# Launch_Tower_Ignition_Board_v6-0.net
KiCad netlist of a schematic drawn in EAGLE
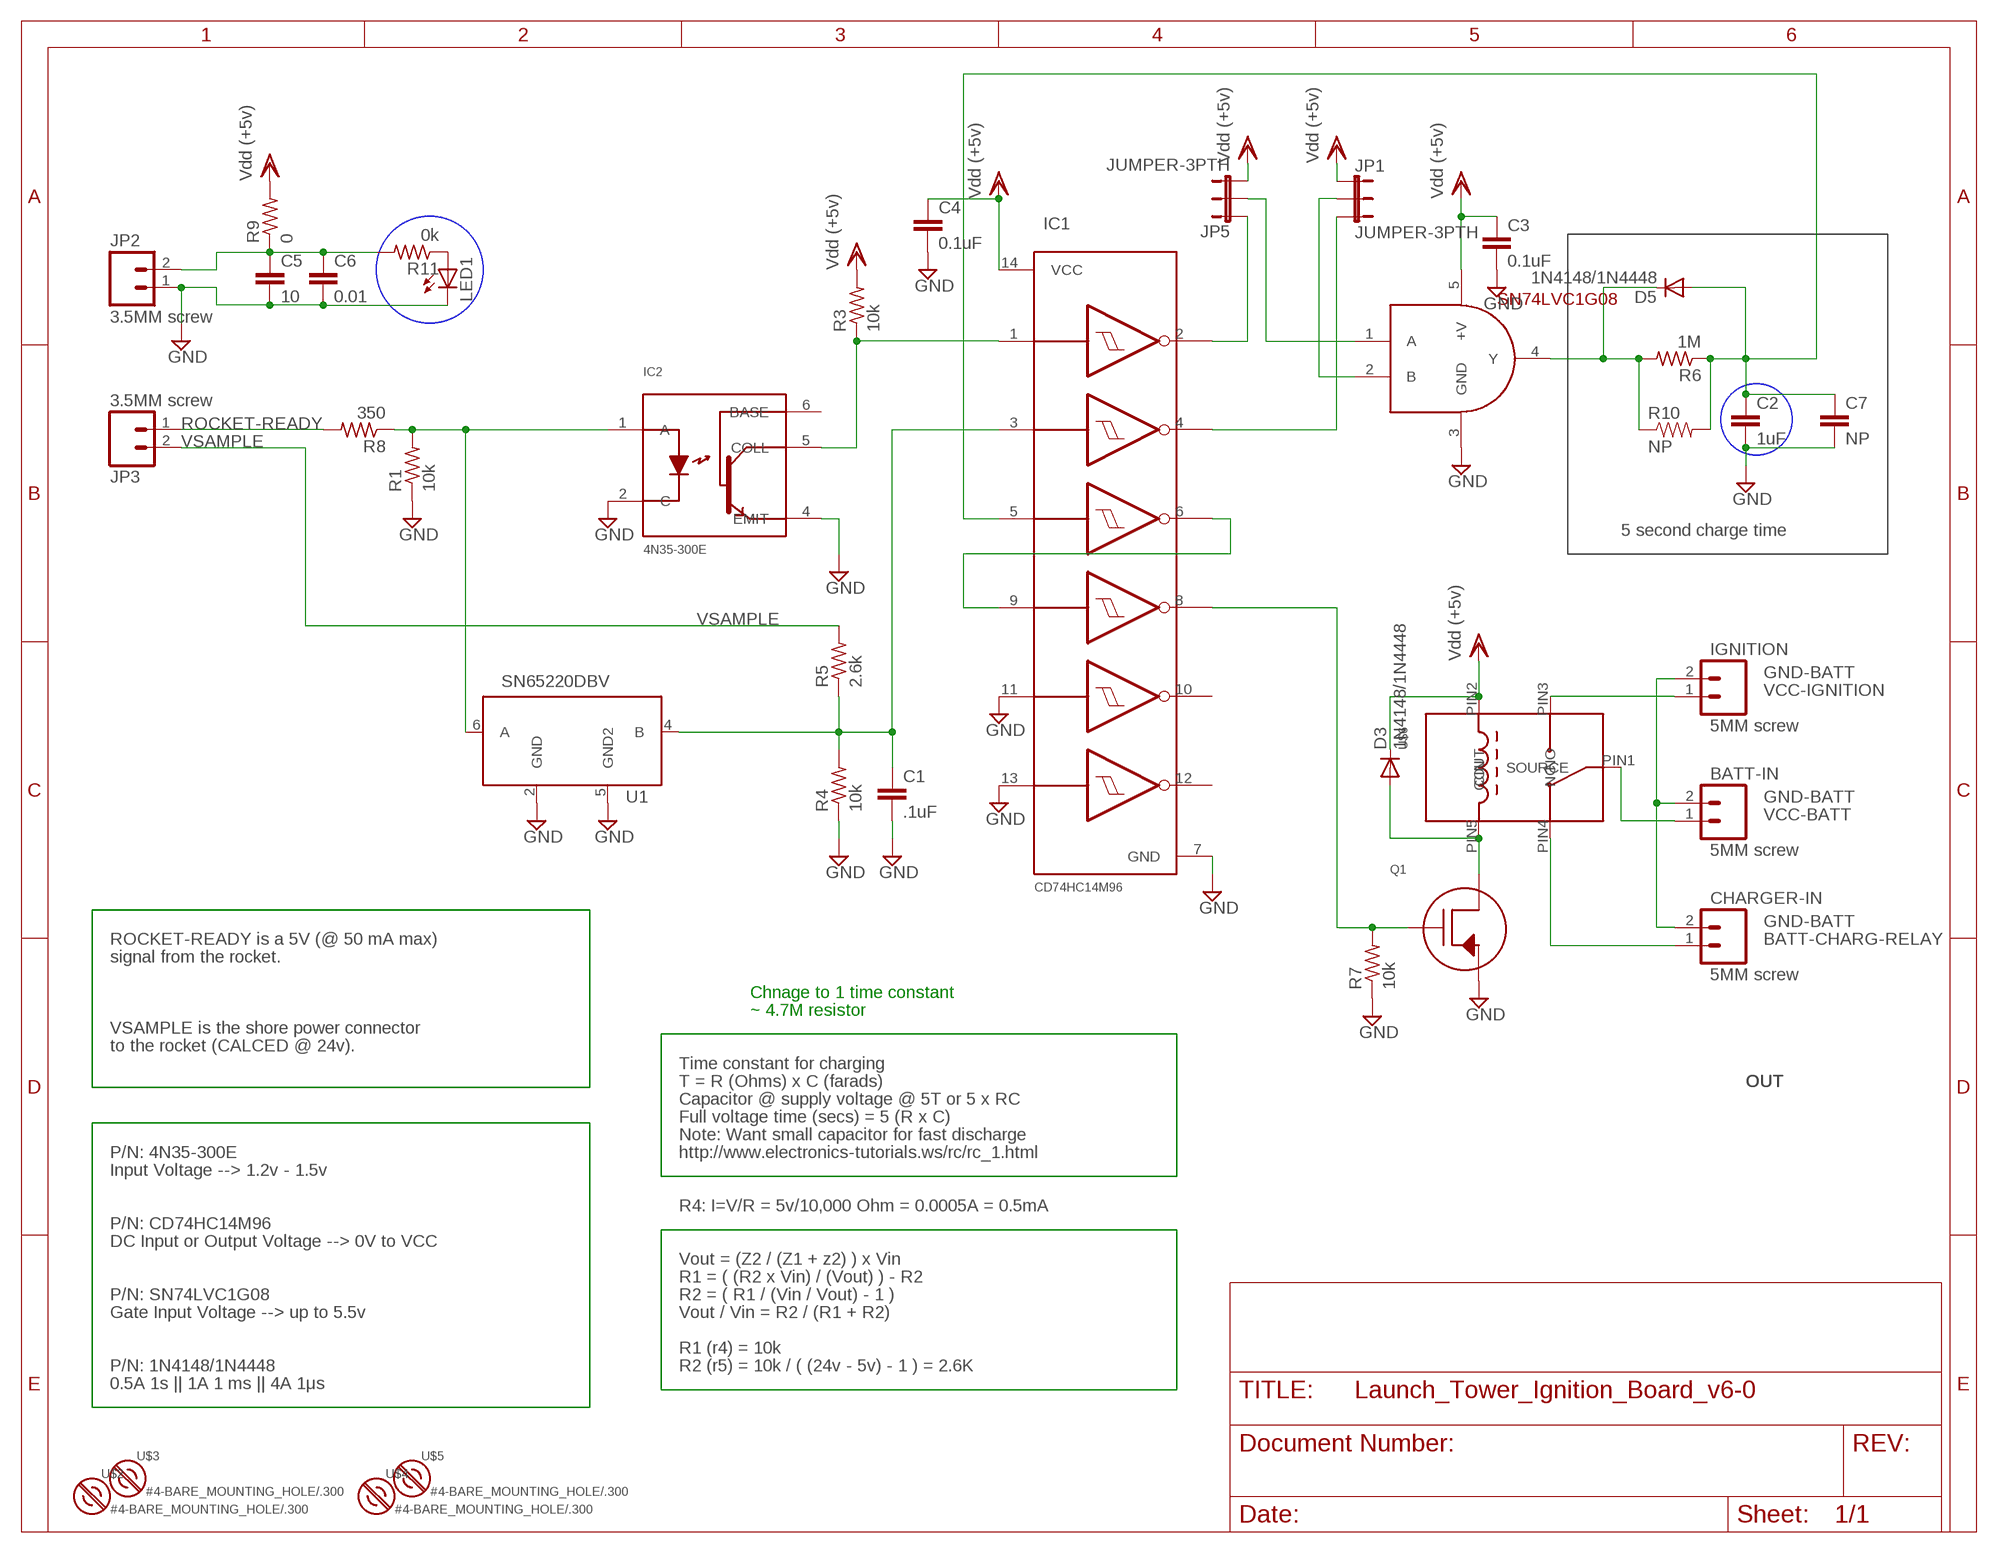
[diagram p0: schematic, sheet 1]

(export (version "E")
  (design (tool "Eeschema 10.0.6"))
  (components
    (comp (ref "BATT-IN")
      (value "5MM screw")
      (footprint "eagle-import:SCREWTERMINAL-5MM-2")
      (libsource (lib "eagle-import") (part "M025MM"))
    )
    (comp (ref "C1")
      (value ".1uF")
      (footprint "eagle-import:0805-B-NOSILK")
      (libsource (lib "eagle-import") (part "C-EU0805-B-NOSILK"))
    )
    (comp (ref "C2")
      (value "1uF")
      (footprint "eagle-import:0805-B-NOSILK")
      (libsource (lib "eagle-import") (part "C-EU0805-B-NOSILK"))
    )
    (comp (ref "C3")
      (value "0.1uF")
      (footprint "eagle-import:0805-B-NOSILK")
      (libsource (lib "eagle-import") (part "C-EU0805-B-NOSILK"))
    )
    (comp (ref "C4")
      (value "0.1uF")
      (footprint "eagle-import:0805-B-NOSILK")
      (libsource (lib "eagle-import") (part "C-EU0805-B-NOSILK"))
    )
    (comp (ref "C5")
      (value "10")
      (footprint "eagle-import:0805-B-NOSILK")
      (libsource (lib "eagle-import") (part "C-EU0805-B-NOSILK"))
    )
    (comp (ref "C6")
      (value "0.01")
      (footprint "eagle-import:0805-B-NOSILK")
      (libsource (lib "eagle-import") (part "C-EU0805-B-NOSILK"))
    )
    (comp (ref "C7")
      (value "NP")
      (footprint "eagle-import:CAP-PTH-SMALL")
      (libsource (lib "eagle-import") (part "CAPPTH"))
    )
    (comp (ref "CHARGER-IN")
      (value "5MM screw")
      (footprint "eagle-import:SCREWTERMINAL-5MM-2")
      (libsource (lib "eagle-import") (part "M025MM"))
    )
    (comp (ref "D3")
      (value "1N4148/1N4448")
      (footprint "eagle-import:DIODE-1N4001")
      (libsource (lib "eagle-import") (part "DIODEPTH"))
    )
    (comp (ref "D5")
      (value "1N4148/1N4448")
      (footprint "eagle-import:DIODE-1N4001")
      (libsource (lib "eagle-import") (part "DIODEPTH"))
    )
    (comp (ref "IC1")
      (value "INVERT GATES")
      (footprint "eagle-import:INVERTSOIC14")
      (libsource (lib "eagle-import") (part "HEX_INV_SHMITT_TRIG"))
    )
    (comp (ref "IC2")
      (value "OPTOISOLATOR")
      (footprint "eagle-import:4N35-300E")
      (libsource (lib "eagle-import") (part "OPTOISOLATOR"))
    )
    (comp (ref "IGNITION")
      (value "5MM screw")
      (footprint "eagle-import:SCREWTERMINAL-5MM-2")
      (libsource (lib "eagle-import") (part "M025MM"))
    )
    (comp (ref "JP1")
      (value "JUMPER-3PTH")
      (footprint "eagle-import:1X03")
      (libsource (lib "eagle-import") (part "JUMPER-3PTH"))
    )
    (comp (ref "JP2")
      (value "3.5MM screw")
      (footprint "eagle-import:SCREWTERMINAL-3.5MM-2")
      (libsource (lib "eagle-import") (part "M023.5MM"))
    )
    (comp (ref "JP3")
      (value "3.5MM screw")
      (footprint "eagle-import:SCREWTERMINAL-3.5MM-2")
      (libsource (lib "eagle-import") (part "M023.5MM"))
    )
    (comp (ref "JP5")
      (value "JUMPER-3PTH")
      (footprint "eagle-import:1X03")
      (libsource (lib "eagle-import") (part "JUMPER-3PTH"))
    )
    (comp (ref "LED1")
      (value "LED-FKIT-1206")
      (footprint "eagle-import:FKIT-LED-1206")
      (libsource (lib "eagle-import") (part "LED-FKIT-1206"))
    )
    (comp (ref "Q1")
      (value "NMOSFET")
      (footprint "eagle-import:FETSO-8")
      (libsource (lib "eagle-import") (part "NMOSFET"))
    )
    (comp (ref "R1")
      (value "10k")
      (footprint "eagle-import:0805-B-NOSILK")
      (libsource (lib "eagle-import") (part "R-US_0805-B-NOSILK"))
    )
    (comp (ref "R3")
      (value "10k")
      (footprint "eagle-import:0805-B-NOSILK")
      (libsource (lib "eagle-import") (part "R-US_0805-B-NOSILK"))
    )
    (comp (ref "R4")
      (value "10k")
      (footprint "eagle-import:0805-B-NOSILK")
      (libsource (lib "eagle-import") (part "R-US_0805-B-NOSILK"))
    )
    (comp (ref "R5")
      (value "2.6k")
      (footprint "eagle-import:0805-B-NOSILK")
      (libsource (lib "eagle-import") (part "R-US_0805-B-NOSILK"))
    )
    (comp (ref "R6")
      (value "1M")
      (footprint "eagle-import:0805-B-NOSILK")
      (libsource (lib "eagle-import") (part "R-US_0805-B-NOSILK"))
    )
    (comp (ref "R7")
      (value "10k")
      (footprint "eagle-import:0805-B-NOSILK")
      (libsource (lib "eagle-import") (part "R-US_0805-B-NOSILK"))
    )
    (comp (ref "R8")
      (value "350")
      (footprint "eagle-import:0805-B-NOSILK")
      (libsource (lib "eagle-import") (part "R-US_0805-B-NOSILK"))
    )
    (comp (ref "R9")
      (value "0")
      (footprint "eagle-import:0805-B-NOSILK")
      (libsource (lib "eagle-import") (part "R-US_0805-B-NOSILK"))
    )
    (comp (ref "R10")
      (value "NP")
      (footprint "eagle-import:AXIAL-0.4")
      (libsource (lib "eagle-import") (part "RESISTORPTH-1/4W"))
    )
    (comp (ref "R11")
      (value "0k")
      (footprint "eagle-import:0805-B-NOSILK")
      (libsource (lib "eagle-import") (part "R-US_0805-B-NOSILK"))
    )
    (comp (ref "U$1")
      (value "AND GATE")
      (footprint "eagle-import:SOT23-5")
      (libsource (lib "eagle-import") (part "SN74LVC1G08"))
    )
    (comp (ref "U$2")
      (value "#4-BARE_MOUNTING_HOLE/.300")
      (footprint "eagle-import:#4_.300-BARE+STD_NUT_OR_STAR_WASHER")
      (libsource (lib "eagle-import") (part "#4-BARE_MOUNTING_HOLE/.300"))
    )
    (comp (ref "U$3")
      (value "#4-BARE_MOUNTING_HOLE/.300")
      (footprint "eagle-import:#4_.300-BARE+STD_NUT_OR_STAR_WASHER")
      (libsource (lib "eagle-import") (part "#4-BARE_MOUNTING_HOLE/.300"))
    )
    (comp (ref "U$4")
      (value "#4-BARE_MOUNTING_HOLE/.300")
      (footprint "eagle-import:#4_.300-BARE+STD_NUT_OR_STAR_WASHER")
      (libsource (lib "eagle-import") (part "#4-BARE_MOUNTING_HOLE/.300"))
    )
    (comp (ref "U$5")
      (value "#4-BARE_MOUNTING_HOLE/.300")
      (footprint "eagle-import:#4_.300-BARE+STD_NUT_OR_STAR_WASHER")
      (libsource (lib "eagle-import") (part "#4-BARE_MOUNTING_HOLE/.300"))
    )
    (comp (ref "U$6")
      (value "RELAY-2")
      (footprint "eagle-import:G5LA")
      (libsource (lib "eagle-import") (part "RELAY-2"))
    )
    (comp (ref "U1")
      (value "SN65220DBV")
      (footprint "eagle-import:SOT23-6L")
      (libsource (lib "eagle-import") (part "SN65220DBV"))
    )
  )
  (nets
    (net (code "1") (name "/BATT-CHARG-RELAY") (class "Default")
      (node (ref "CHARGER-IN") (pin "1") (pinfunction "1_1") (pintype "passive"))
      (node (ref "U$6") (pin "PIN4") (pinfunction "NC_PIN4") (pintype "bidirectional"))
    )
    (net (code "2") (name "/GND-BATT") (class "Default")
      (node (ref "BATT-IN") (pin "2") (pinfunction "2_2") (pintype "passive"))
      (node (ref "CHARGER-IN") (pin "2") (pinfunction "2_2") (pintype "passive"))
      (node (ref "IGNITION") (pin "2") (pinfunction "2_2") (pintype "passive"))
    )
    (net (code "3") (name "/ROCKET-READY") (class "Default")
      (node (ref "IC2") (pin "1") (pinfunction "A_1") (pintype "bidirectional"))
      (node (ref "R1") (pin "2") (pinfunction "2_2") (pintype "passive"))
      (node (ref "R8") (pin "1") (pinfunction "1_1") (pintype "passive"))
      (node (ref "U1") (pin "6") (pinfunction "A_6") (pintype "passive"))
    )
    (net (code "4") (name "/VCC-BATT") (class "Default")
      (node (ref "BATT-IN") (pin "1") (pinfunction "1_1") (pintype "passive"))
      (node (ref "U$6") (pin "PIN1") (pinfunction "SOURCE_PIN1") (pintype "bidirectional"))
    )
    (net (code "5") (name "/VCC-IGNITION") (class "Default")
      (node (ref "IGNITION") (pin "1") (pinfunction "1_1") (pintype "passive"))
      (node (ref "U$6") (pin "PIN3") (pinfunction "NO_PIN3") (pintype "bidirectional"))
    )
    (net (code "6") (name "/VSAMPLE") (class "Default")
      (node (ref "JP3") (pin "2") (pinfunction "2_2") (pintype "passive"))
      (node (ref "R5") (pin "2") (pinfunction "2_2") (pintype "passive"))
    )
    (net (code "7") (name "GND") (class "Default")
      (node (ref "C1") (pin "2") (pinfunction "2_2") (pintype "passive"))
      (node (ref "C2") (pin "2") (pinfunction "2_2") (pintype "passive"))
      (node (ref "C3") (pin "2") (pinfunction "2_2") (pintype "passive"))
      (node (ref "C4") (pin "2") (pinfunction "2_2") (pintype "passive"))
      (node (ref "C5") (pin "2") (pinfunction "2_2") (pintype "passive"))
      (node (ref "C6") (pin "2") (pinfunction "2_2") (pintype "passive"))
      (node (ref "C7") (pin "2") (pinfunction "2_2") (pintype "passive"))
      (node (ref "IC1") (pin "11") (pinfunction "5A_11") (pintype "input"))
      (node (ref "IC1") (pin "13") (pinfunction "6A_13") (pintype "input"))
      (node (ref "IC1") (pin "7") (pinfunction "GND_7") (pintype "bidirectional"))
      (node (ref "IC2") (pin "2") (pinfunction "C_2") (pintype "bidirectional"))
      (node (ref "IC2") (pin "4") (pinfunction "EMIT_4") (pintype "bidirectional"))
      (node (ref "JP2") (pin "1") (pinfunction "1_1") (pintype "passive"))
      (node (ref "LED1") (pin "C") (pinfunction "C_C") (pintype "passive"))
      (node (ref "Q1") (pin "1") (pinfunction "SOURCE_1") (pintype "bidirectional"))
      (node (ref "R1") (pin "1") (pinfunction "1_1") (pintype "passive"))
      (node (ref "R4") (pin "1") (pinfunction "1_1") (pintype "passive"))
      (node (ref "R7") (pin "1") (pinfunction "1_1") (pintype "passive"))
      (node (ref "U$1") (pin "3") (pinfunction "GND_3") (pintype "bidirectional"))
      (node (ref "U1") (pin "2") (pinfunction "GND_2") (pintype "power_in"))
      (node (ref "U1") (pin "5") (pinfunction "GND2_5") (pintype "power_in"))
    )
    (net (code "8") (name "Net-(C5-Pad1)") (class "Default")
      (node (ref "C5") (pin "1") (pinfunction "1_1") (pintype "passive"))
      (node (ref "C6") (pin "1") (pinfunction "1_1") (pintype "passive"))
      (node (ref "JP2") (pin "2") (pinfunction "2_2") (pintype "passive"))
      (node (ref "R11") (pin "2") (pinfunction "2_2") (pintype "passive"))
      (node (ref "R9") (pin "1") (pinfunction "1_1") (pintype "passive"))
    )
    (net (code "9") (name "Net-(IC1-1A)") (class "Default")
      (node (ref "IC1") (pin "1") (pinfunction "1A_1") (pintype "input"))
      (node (ref "IC2") (pin "5") (pinfunction "COLL_5") (pintype "bidirectional"))
      (node (ref "R3") (pin "1") (pinfunction "1_1") (pintype "passive"))
    )
    (net (code "10") (name "Net-(IC1-1Y)") (class "Default")
      (node (ref "IC1") (pin "2") (pinfunction "1Y_2") (pintype "output"))
      (node (ref "JP5") (pin "1") (pinfunction "1_1") (pintype "passive"))
    )
    (net (code "11") (name "Net-(IC1-2A)") (class "Default")
      (node (ref "C1") (pin "1") (pinfunction "1_1") (pintype "passive"))
      (node (ref "IC1") (pin "3") (pinfunction "2A_3") (pintype "input"))
      (node (ref "R4") (pin "2") (pinfunction "2_2") (pintype "passive"))
      (node (ref "R5") (pin "1") (pinfunction "1_1") (pintype "passive"))
      (node (ref "U1") (pin "4") (pinfunction "B_4") (pintype "passive"))
    )
    (net (code "12") (name "Net-(IC1-2Y)") (class "Default")
      (node (ref "IC1") (pin "4") (pinfunction "2Y_4") (pintype "output"))
      (node (ref "JP1") (pin "3") (pinfunction "3_3") (pintype "passive"))
    )
    (net (code "13") (name "Net-(IC1-3A)") (class "Default")
      (node (ref "C2") (pin "1") (pinfunction "1_1") (pintype "passive"))
      (node (ref "C7") (pin "1") (pinfunction "1_1") (pintype "passive"))
      (node (ref "D5") (pin "A") (pinfunction "A_A") (pintype "passive"))
      (node (ref "IC1") (pin "5") (pinfunction "3A_5") (pintype "input"))
      (node (ref "R10") (pin "P$2") (pinfunction "2_P$2") (pintype "passive"))
      (node (ref "R6") (pin "1") (pinfunction "1_1") (pintype "passive"))
    )
    (net (code "14") (name "Net-(IC1-3Y)") (class "Default")
      (node (ref "IC1") (pin "6") (pinfunction "3Y_6") (pintype "output"))
      (node (ref "IC1") (pin "9") (pinfunction "4A_9") (pintype "input"))
    )
    (net (code "15") (name "Net-(IC1-4Y)") (class "Default")
      (node (ref "IC1") (pin "8") (pinfunction "4Y_8") (pintype "output"))
      (node (ref "Q1") (pin "4") (pinfunction "GATE_4") (pintype "bidirectional"))
      (node (ref "R7") (pin "2") (pinfunction "2_2") (pintype "passive"))
    )
    (net (code "16") (name "Net-(JP3-Pad1)") (class "Default")
      (node (ref "JP3") (pin "1") (pinfunction "1_1") (pintype "passive"))
      (node (ref "R8") (pin "2") (pinfunction "2_2") (pintype "passive"))
    )
    (net (code "17") (name "Net-(LED1-PadA)") (class "Default")
      (node (ref "LED1") (pin "A") (pinfunction "A_A") (pintype "passive"))
      (node (ref "R11") (pin "1") (pinfunction "1_1") (pintype "passive"))
    )
    (net (code "18") (name "Net-(Q1-DRAIN)") (class "Default")
      (node (ref "D3") (pin "A") (pinfunction "A_A") (pintype "passive"))
      (node (ref "Q1") (pin "5") (pinfunction "DRAIN_5") (pintype "bidirectional"))
      (node (ref "U$6") (pin "PIN5") (pinfunction "CIN_PIN5") (pintype "bidirectional"))
    )
    (net (code "19") (name "Net-(R10-1)") (class "Default")
      (node (ref "D5") (pin "C") (pinfunction "C_C") (pintype "passive"))
      (node (ref "R10") (pin "P$1") (pinfunction "1_P$1") (pintype "passive"))
      (node (ref "R6") (pin "2") (pinfunction "2_2") (pintype "passive"))
      (node (ref "U$1") (pin "4") (pinfunction "Y_4") (pintype "bidirectional"))
    )
    (net (code "20") (name "Net-(U$1-A)") (class "Default")
      (node (ref "JP5") (pin "2") (pinfunction "2_2") (pintype "passive"))
      (node (ref "U$1") (pin "1") (pinfunction "A_1") (pintype "bidirectional"))
    )
    (net (code "21") (name "Net-(U$1-B)") (class "Default")
      (node (ref "JP1") (pin "2") (pinfunction "2_2") (pintype "passive"))
      (node (ref "U$1") (pin "2") (pinfunction "B_2") (pintype "bidirectional"))
    )
    (net (code "22") (name "Vdd (+5v)") (class "Default")
      (node (ref "C3") (pin "1") (pinfunction "1_1") (pintype "passive"))
      (node (ref "C4") (pin "1") (pinfunction "1_1") (pintype "passive"))
      (node (ref "D3") (pin "C") (pinfunction "C_C") (pintype "passive"))
      (node (ref "IC1") (pin "14") (pinfunction "VCC_14") (pintype "bidirectional"))
      (node (ref "JP1") (pin "1") (pinfunction "1_1") (pintype "passive"))
      (node (ref "JP5") (pin "3") (pinfunction "3_3") (pintype "passive"))
      (node (ref "R3") (pin "2") (pinfunction "2_2") (pintype "passive"))
      (node (ref "R9") (pin "2") (pinfunction "2_2") (pintype "passive"))
      (node (ref "U$1") (pin "5") (pinfunction "+V_5") (pintype "bidirectional"))
      (node (ref "U$6") (pin "PIN2") (pinfunction "COUT_PIN2") (pintype "bidirectional"))
    )
    (net (code "23") (name "unconnected-(IC1-5Y-Pad10)") (class "Default")
      (node (ref "IC1") (pin "10") (pinfunction "5Y_10") (pintype "output"))
    )
    (net (code "24") (name "unconnected-(IC1-6Y-Pad12)") (class "Default")
      (node (ref "IC1") (pin "12") (pinfunction "6Y_12") (pintype "output"))
    )
    (net (code "25") (name "unconnected-(IC2-BASE-Pad6)") (class "Default")
      (node (ref "IC2") (pin "6") (pinfunction "BASE_6") (pintype "bidirectional"))
    )
  )
)
